# emonPi_v2_0_0_CT_ext.net
KiCad netlist of a schematic drawn in EAGLE
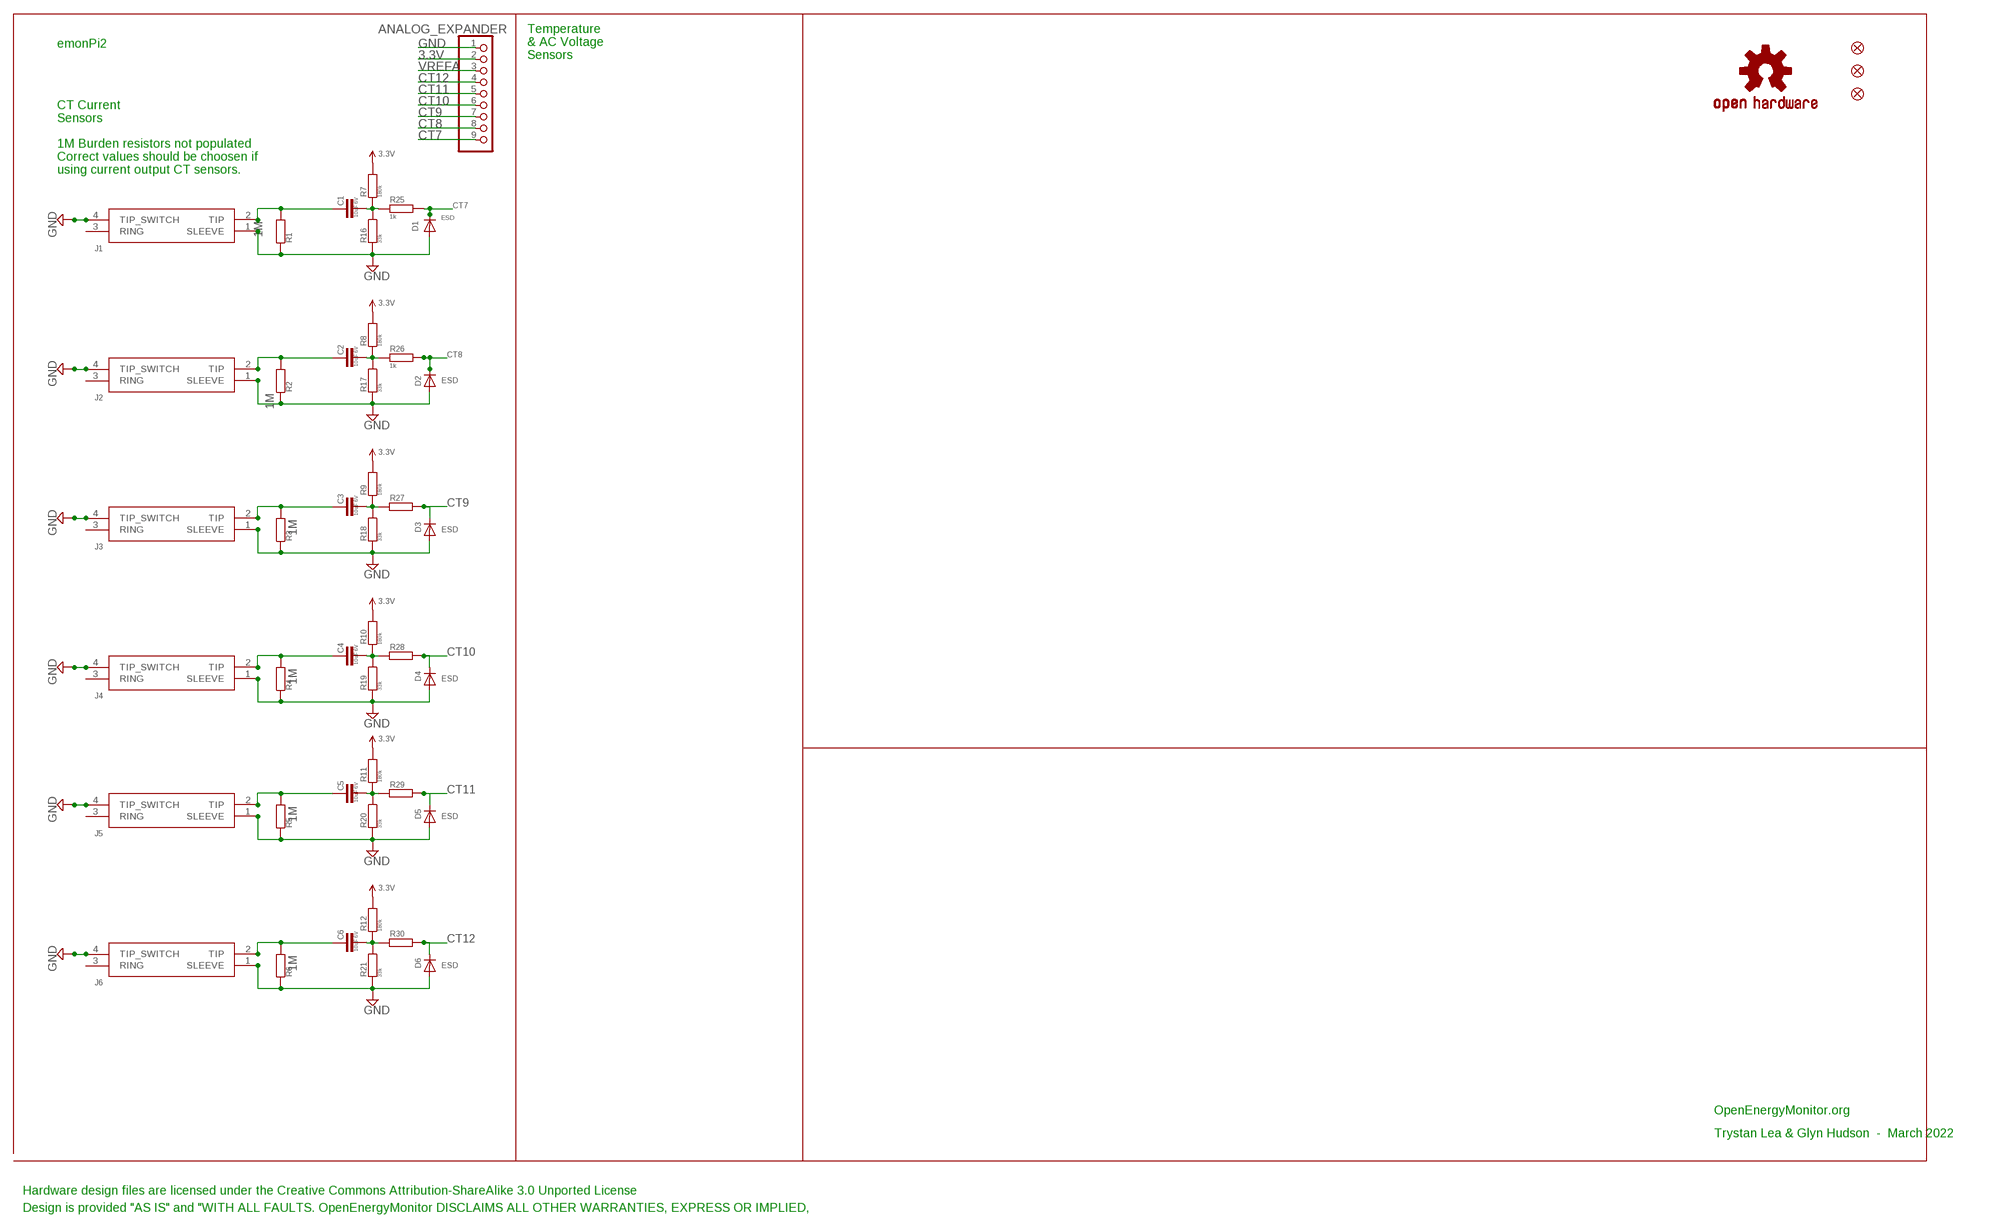
[diagram p0: schematic, sheet 1]

(export (version "E")
  (design (tool "Eeschema 10.0.6"))
  (components
    (comp (ref "ANALOG_EXPANDER")
      (value "PINHD-1X9")
      (footprint "eagle-import:1X09-BIG")
      (libsource (lib "eagle-import") (part "PINHD-1X9"))
    )
    (comp (ref "C1")
      (value "10uF 6V")
      (footprint "eagle-import:C0603")
      (libsource (lib "eagle-import") (part "C-EUC0603"))
    )
    (comp (ref "C2")
      (value "10uF 6V")
      (footprint "eagle-import:C0603")
      (libsource (lib "eagle-import") (part "C-EUC0603"))
    )
    (comp (ref "C3")
      (value "10uF 6V")
      (footprint "eagle-import:C0603")
      (libsource (lib "eagle-import") (part "C-EUC0603"))
    )
    (comp (ref "C4")
      (value "10uF 6V")
      (footprint "eagle-import:C0603")
      (libsource (lib "eagle-import") (part "C-EUC0603"))
    )
    (comp (ref "C5")
      (value "10uF 6V")
      (footprint "eagle-import:C0603")
      (libsource (lib "eagle-import") (part "C-EUC0603"))
    )
    (comp (ref "C6")
      (value "10uF 6V")
      (footprint "eagle-import:C0603")
      (libsource (lib "eagle-import") (part "C-EUC0603"))
    )
    (comp (ref "D1")
      (value "ESD")
      (footprint "eagle-import:SOD-523")
      (libsource (lib "eagle-import") (part "DIODESOD-523"))
    )
    (comp (ref "D2")
      (value "ESD")
      (footprint "eagle-import:SOD-523")
      (libsource (lib "eagle-import") (part "DIODESOD-523"))
    )
    (comp (ref "D3")
      (value "ESD")
      (footprint "eagle-import:SOD-523")
      (libsource (lib "eagle-import") (part "DIODESOD-523"))
    )
    (comp (ref "D4")
      (value "ESD")
      (footprint "eagle-import:SOD-523")
      (libsource (lib "eagle-import") (part "DIODESOD-523"))
    )
    (comp (ref "D5")
      (value "ESD")
      (footprint "eagle-import:SOD-523")
      (libsource (lib "eagle-import") (part "DIODESOD-523"))
    )
    (comp (ref "D6")
      (value "ESD")
      (footprint "eagle-import:SOD-523")
      (libsource (lib "eagle-import") (part "DIODESOD-523"))
    )
    (comp (ref "FD1")
      (value "FIDUCIAL1X2")
      (footprint "eagle-import:FIDUCIAL-1X2")
      (libsource (lib "eagle-import") (part "FIDUCIAL1X2"))
    )
    (comp (ref "FD2")
      (value "FIDUCIAL1X2")
      (footprint "eagle-import:FIDUCIAL-1X2")
      (libsource (lib "eagle-import") (part "FIDUCIAL1X2"))
    )
    (comp (ref "FD3")
      (value "FIDUCIAL1X2")
      (footprint "eagle-import:FIDUCIAL-1X2")
      (libsource (lib "eagle-import") (part "FIDUCIAL1X2"))
    )
    (comp (ref "J1")
      (value "SJ-3524-SMT-TR")
      (footprint "eagle-import:SJ-3524-SMT-TR")
      (fields (field (name "MOUSER_PART_NUMBER") "490-SJ-3524-SMT-TR"))
      (libsource (lib "eagle-import") (part "SJ-3524-SMT-TR"))
    )
    (comp (ref "J2")
      (value "SJ-3524-SMT-TR")
      (footprint "eagle-import:SJ-3524-SMT-TR")
      (fields (field (name "MOUSER_PART_NUMBER") "490-SJ-3524-SMT-TR"))
      (libsource (lib "eagle-import") (part "SJ-3524-SMT-TR"))
    )
    (comp (ref "J3")
      (value "SJ-3524-SMT-TR")
      (footprint "eagle-import:SJ-3524-SMT-TR")
      (fields (field (name "MOUSER_PART_NUMBER") "490-SJ-3524-SMT-TR"))
      (libsource (lib "eagle-import") (part "SJ-3524-SMT-TR"))
    )
    (comp (ref "J4")
      (value "SJ-3524-SMT-TR")
      (footprint "eagle-import:SJ-3524-SMT-TR")
      (fields (field (name "MOUSER_PART_NUMBER") "490-SJ-3524-SMT-TR"))
      (libsource (lib "eagle-import") (part "SJ-3524-SMT-TR"))
    )
    (comp (ref "J5")
      (value "SJ-3524-SMT-TR")
      (footprint "eagle-import:SJ-3524-SMT-TR")
      (fields (field (name "MOUSER_PART_NUMBER") "490-SJ-3524-SMT-TR"))
      (libsource (lib "eagle-import") (part "SJ-3524-SMT-TR"))
    )
    (comp (ref "J6")
      (value "SJ-3524-SMT-TR")
      (footprint "eagle-import:SJ-3524-SMT-TR")
      (fields (field (name "MOUSER_PART_NUMBER") "490-SJ-3524-SMT-TR"))
      (libsource (lib "eagle-import") (part "SJ-3524-SMT-TR"))
    )
    (comp (ref "LOGO1")
      (value "OSHW-LOGOS-COPPER")
      (footprint "eagle-import:OSHW-LOGO-S_COPPER")
      (libsource (lib "eagle-import") (part "OSHW-LOGOS-COPPER"))
    )
    (comp (ref "R1")
      (value "1M")
      (footprint "eagle-import:R1206")
      (libsource (lib "eagle-import") (part "R-EU_R1206"))
    )
    (comp (ref "R2")
      (value "1M")
      (footprint "eagle-import:R1206")
      (libsource (lib "eagle-import") (part "R-EU_R1206"))
    )
    (comp (ref "R3")
      (value "1M")
      (footprint "eagle-import:R1206")
      (libsource (lib "eagle-import") (part "R-EU_R1206"))
    )
    (comp (ref "R4")
      (value "1M")
      (footprint "eagle-import:R1206")
      (libsource (lib "eagle-import") (part "R-EU_R1206"))
    )
    (comp (ref "R5")
      (value "1M")
      (footprint "eagle-import:R1206")
      (libsource (lib "eagle-import") (part "R-EU_R1206"))
    )
    (comp (ref "R6")
      (value "1M")
      (footprint "eagle-import:R1206")
      (libsource (lib "eagle-import") (part "R-EU_R1206"))
    )
    (comp (ref "R7")
      (value "180k")
      (footprint "eagle-import:R0603")
      (libsource (lib "eagle-import") (part "R-EU_R0603"))
    )
    (comp (ref "R8")
      (value "180k")
      (footprint "eagle-import:R0603")
      (libsource (lib "eagle-import") (part "R-EU_R0603"))
    )
    (comp (ref "R9")
      (value "180k")
      (footprint "eagle-import:R0603")
      (libsource (lib "eagle-import") (part "R-EU_R0603"))
    )
    (comp (ref "R10")
      (value "180k")
      (footprint "eagle-import:R0603")
      (libsource (lib "eagle-import") (part "R-EU_R0603"))
    )
    (comp (ref "R11")
      (value "180k")
      (footprint "eagle-import:R0603")
      (libsource (lib "eagle-import") (part "R-EU_R0603"))
    )
    (comp (ref "R12")
      (value "180k")
      (footprint "eagle-import:R0603")
      (libsource (lib "eagle-import") (part "R-EU_R0603"))
    )
    (comp (ref "R16")
      (value "33k")
      (footprint "eagle-import:R0603")
      (libsource (lib "eagle-import") (part "R-EU_R0603"))
    )
    (comp (ref "R17")
      (value "33k")
      (footprint "eagle-import:R0603")
      (libsource (lib "eagle-import") (part "R-EU_R0603"))
    )
    (comp (ref "R18")
      (value "33k")
      (footprint "eagle-import:R0603")
      (libsource (lib "eagle-import") (part "R-EU_R0603"))
    )
    (comp (ref "R19")
      (value "33k")
      (footprint "eagle-import:R0603")
      (libsource (lib "eagle-import") (part "R-EU_R0603"))
    )
    (comp (ref "R20")
      (value "33k")
      (footprint "eagle-import:R0603")
      (libsource (lib "eagle-import") (part "R-EU_R0603"))
    )
    (comp (ref "R21")
      (value "33k")
      (footprint "eagle-import:R0603")
      (libsource (lib "eagle-import") (part "R-EU_R0603"))
    )
    (comp (ref "R25")
      (value "1k")
      (footprint "eagle-import:R0603")
      (libsource (lib "eagle-import") (part "R-EU_R0603"))
    )
    (comp (ref "R26")
      (value "1k")
      (footprint "eagle-import:R0603")
      (libsource (lib "eagle-import") (part "R-EU_R0603"))
    )
    (comp (ref "R27")
      (value "1k")
      (footprint "eagle-import:R0603")
      (libsource (lib "eagle-import") (part "R-EU_R0603"))
    )
    (comp (ref "R28")
      (value "1k")
      (footprint "eagle-import:R0603")
      (libsource (lib "eagle-import") (part "R-EU_R0603"))
    )
    (comp (ref "R29")
      (value "1k")
      (footprint "eagle-import:R0603")
      (libsource (lib "eagle-import") (part "R-EU_R0603"))
    )
    (comp (ref "R30")
      (value "1k")
      (footprint "eagle-import:R0603")
      (libsource (lib "eagle-import") (part "R-EU_R0603"))
    )
  )
  (nets
    (net (code "1") (name "/CT7") (class "Default")
      (node (ref "ANALOG_EXPANDER") (pin "9") (pinfunction "9_9") (pintype "passive"))
      (node (ref "D1") (pin "K") (pinfunction "C_K") (pintype "passive"))
      (node (ref "R25") (pin "2") (pinfunction "2_2") (pintype "passive"))
    )
    (net (code "2") (name "/CT8") (class "Default")
      (node (ref "ANALOG_EXPANDER") (pin "8") (pinfunction "8_8") (pintype "passive"))
      (node (ref "D2") (pin "K") (pinfunction "C_K") (pintype "passive"))
      (node (ref "R26") (pin "2") (pinfunction "2_2") (pintype "passive"))
    )
    (net (code "3") (name "/CT9") (class "Default")
      (node (ref "ANALOG_EXPANDER") (pin "7") (pinfunction "7_7") (pintype "passive"))
      (node (ref "D3") (pin "K") (pinfunction "C_K") (pintype "passive"))
      (node (ref "R27") (pin "1") (pinfunction "1_1") (pintype "passive"))
    )
    (net (code "4") (name "/CT10") (class "Default")
      (node (ref "ANALOG_EXPANDER") (pin "6") (pinfunction "6_6") (pintype "passive"))
      (node (ref "D4") (pin "K") (pinfunction "C_K") (pintype "passive"))
      (node (ref "R28") (pin "1") (pinfunction "1_1") (pintype "passive"))
    )
    (net (code "5") (name "/CT11") (class "Default")
      (node (ref "ANALOG_EXPANDER") (pin "5") (pinfunction "5_5") (pintype "passive"))
      (node (ref "D5") (pin "K") (pinfunction "C_K") (pintype "passive"))
      (node (ref "R29") (pin "1") (pinfunction "1_1") (pintype "passive"))
    )
    (net (code "6") (name "/CT12") (class "Default")
      (node (ref "ANALOG_EXPANDER") (pin "4") (pinfunction "4_4") (pintype "passive"))
      (node (ref "D6") (pin "K") (pinfunction "C_K") (pintype "passive"))
      (node (ref "R30") (pin "1") (pinfunction "1_1") (pintype "passive"))
    )
    (net (code "7") (name "/VREFA") (class "Default")
      (node (ref "ANALOG_EXPANDER") (pin "3") (pinfunction "3_3") (pintype "passive"))
    )
    (net (code "8") (name "3.3V") (class "Default")
      (node (ref "ANALOG_EXPANDER") (pin "2") (pinfunction "2_2") (pintype "passive"))
      (node (ref "R10") (pin "2") (pinfunction "2_2") (pintype "passive"))
      (node (ref "R11") (pin "2") (pinfunction "2_2") (pintype "passive"))
      (node (ref "R12") (pin "2") (pinfunction "2_2") (pintype "passive"))
      (node (ref "R7") (pin "2") (pinfunction "2_2") (pintype "passive"))
      (node (ref "R8") (pin "2") (pinfunction "2_2") (pintype "passive"))
      (node (ref "R9") (pin "2") (pinfunction "2_2") (pintype "passive"))
    )
    (net (code "9") (name "GND") (class "Default")
      (node (ref "ANALOG_EXPANDER") (pin "1") (pinfunction "1_1") (pintype "passive"))
      (node (ref "D1") (pin "A") (pinfunction "A_A") (pintype "passive"))
      (node (ref "D2") (pin "A") (pinfunction "A_A") (pintype "passive"))
      (node (ref "D3") (pin "A") (pinfunction "A_A") (pintype "passive"))
      (node (ref "D4") (pin "A") (pinfunction "A_A") (pintype "passive"))
      (node (ref "D5") (pin "A") (pinfunction "A_A") (pintype "passive"))
      (node (ref "D6") (pin "A") (pinfunction "A_A") (pintype "passive"))
      (node (ref "J1") (pin "1") (pinfunction "SLEEVE_1") (pintype "bidirectional"))
      (node (ref "J1") (pin "4") (pinfunction "TIP_SWITCH_4") (pintype "bidirectional"))
      (node (ref "J2") (pin "1") (pinfunction "SLEEVE_1") (pintype "bidirectional"))
      (node (ref "J2") (pin "4") (pinfunction "TIP_SWITCH_4") (pintype "bidirectional"))
      (node (ref "J3") (pin "1") (pinfunction "SLEEVE_1") (pintype "bidirectional"))
      (node (ref "J3") (pin "4") (pinfunction "TIP_SWITCH_4") (pintype "bidirectional"))
      (node (ref "J4") (pin "1") (pinfunction "SLEEVE_1") (pintype "bidirectional"))
      (node (ref "J4") (pin "4") (pinfunction "TIP_SWITCH_4") (pintype "bidirectional"))
      (node (ref "J5") (pin "1") (pinfunction "SLEEVE_1") (pintype "bidirectional"))
      (node (ref "J5") (pin "4") (pinfunction "TIP_SWITCH_4") (pintype "bidirectional"))
      (node (ref "J6") (pin "1") (pinfunction "SLEEVE_1") (pintype "bidirectional"))
      (node (ref "J6") (pin "4") (pinfunction "TIP_SWITCH_4") (pintype "bidirectional"))
      (node (ref "R1") (pin "1") (pinfunction "1_1") (pintype "passive"))
      (node (ref "R16") (pin "2") (pinfunction "2_2") (pintype "passive"))
      (node (ref "R17") (pin "2") (pinfunction "2_2") (pintype "passive"))
      (node (ref "R18") (pin "2") (pinfunction "2_2") (pintype "passive"))
      (node (ref "R19") (pin "2") (pinfunction "2_2") (pintype "passive"))
      (node (ref "R2") (pin "1") (pinfunction "1_1") (pintype "passive"))
      (node (ref "R20") (pin "2") (pinfunction "2_2") (pintype "passive"))
      (node (ref "R21") (pin "2") (pinfunction "2_2") (pintype "passive"))
      (node (ref "R3") (pin "1") (pinfunction "1_1") (pintype "passive"))
      (node (ref "R4") (pin "1") (pinfunction "1_1") (pintype "passive"))
      (node (ref "R5") (pin "1") (pinfunction "1_1") (pintype "passive"))
      (node (ref "R6") (pin "1") (pinfunction "1_1") (pintype "passive"))
    )
    (net (code "10") (name "Net-(C1-Pad2)") (class "Default")
      (node (ref "C1") (pin "2") (pinfunction "2_2") (pintype "passive"))
      (node (ref "R16") (pin "1") (pinfunction "1_1") (pintype "passive"))
      (node (ref "R25") (pin "1") (pinfunction "1_1") (pintype "passive"))
      (node (ref "R7") (pin "1") (pinfunction "1_1") (pintype "passive"))
    )
    (net (code "11") (name "Net-(C2-Pad2)") (class "Default")
      (node (ref "C2") (pin "2") (pinfunction "2_2") (pintype "passive"))
      (node (ref "R17") (pin "1") (pinfunction "1_1") (pintype "passive"))
      (node (ref "R26") (pin "1") (pinfunction "1_1") (pintype "passive"))
      (node (ref "R8") (pin "1") (pinfunction "1_1") (pintype "passive"))
    )
    (net (code "12") (name "Net-(C3-Pad2)") (class "Default")
      (node (ref "C3") (pin "2") (pinfunction "2_2") (pintype "passive"))
      (node (ref "R18") (pin "1") (pinfunction "1_1") (pintype "passive"))
      (node (ref "R27") (pin "2") (pinfunction "2_2") (pintype "passive"))
      (node (ref "R9") (pin "1") (pinfunction "1_1") (pintype "passive"))
    )
    (net (code "13") (name "Net-(C4-Pad2)") (class "Default")
      (node (ref "C4") (pin "2") (pinfunction "2_2") (pintype "passive"))
      (node (ref "R10") (pin "1") (pinfunction "1_1") (pintype "passive"))
      (node (ref "R19") (pin "1") (pinfunction "1_1") (pintype "passive"))
      (node (ref "R28") (pin "2") (pinfunction "2_2") (pintype "passive"))
    )
    (net (code "14") (name "Net-(C5-Pad2)") (class "Default")
      (node (ref "C5") (pin "2") (pinfunction "2_2") (pintype "passive"))
      (node (ref "R11") (pin "1") (pinfunction "1_1") (pintype "passive"))
      (node (ref "R20") (pin "1") (pinfunction "1_1") (pintype "passive"))
      (node (ref "R29") (pin "2") (pinfunction "2_2") (pintype "passive"))
    )
    (net (code "15") (name "Net-(C6-Pad2)") (class "Default")
      (node (ref "C6") (pin "2") (pinfunction "2_2") (pintype "passive"))
      (node (ref "R12") (pin "1") (pinfunction "1_1") (pintype "passive"))
      (node (ref "R21") (pin "1") (pinfunction "1_1") (pintype "passive"))
      (node (ref "R30") (pin "2") (pinfunction "2_2") (pintype "passive"))
    )
    (net (code "16") (name "Net-(J1-TIP)") (class "Default")
      (node (ref "C1") (pin "1") (pinfunction "1_1") (pintype "passive"))
      (node (ref "J1") (pin "2") (pinfunction "TIP_2") (pintype "bidirectional"))
      (node (ref "R1") (pin "2") (pinfunction "2_2") (pintype "passive"))
    )
    (net (code "17") (name "Net-(J2-TIP)") (class "Default")
      (node (ref "C2") (pin "1") (pinfunction "1_1") (pintype "passive"))
      (node (ref "J2") (pin "2") (pinfunction "TIP_2") (pintype "bidirectional"))
      (node (ref "R2") (pin "2") (pinfunction "2_2") (pintype "passive"))
    )
    (net (code "18") (name "Net-(J3-TIP)") (class "Default")
      (node (ref "C3") (pin "1") (pinfunction "1_1") (pintype "passive"))
      (node (ref "J3") (pin "2") (pinfunction "TIP_2") (pintype "bidirectional"))
      (node (ref "R3") (pin "2") (pinfunction "2_2") (pintype "passive"))
    )
    (net (code "19") (name "Net-(J4-TIP)") (class "Default")
      (node (ref "C4") (pin "1") (pinfunction "1_1") (pintype "passive"))
      (node (ref "J4") (pin "2") (pinfunction "TIP_2") (pintype "bidirectional"))
      (node (ref "R4") (pin "2") (pinfunction "2_2") (pintype "passive"))
    )
    (net (code "20") (name "Net-(J5-TIP)") (class "Default")
      (node (ref "C5") (pin "1") (pinfunction "1_1") (pintype "passive"))
      (node (ref "J5") (pin "2") (pinfunction "TIP_2") (pintype "bidirectional"))
      (node (ref "R5") (pin "2") (pinfunction "2_2") (pintype "passive"))
    )
    (net (code "21") (name "Net-(J6-TIP)") (class "Default")
      (node (ref "C6") (pin "1") (pinfunction "1_1") (pintype "passive"))
      (node (ref "J6") (pin "2") (pinfunction "TIP_2") (pintype "bidirectional"))
      (node (ref "R6") (pin "2") (pinfunction "2_2") (pintype "passive"))
    )
    (net (code "22") (name "unconnected-(J1-RING-Pad3)") (class "Default")
      (node (ref "J1") (pin "3") (pinfunction "RING_3") (pintype "bidirectional"))
    )
    (net (code "23") (name "unconnected-(J2-RING-Pad3)") (class "Default")
      (node (ref "J2") (pin "3") (pinfunction "RING_3") (pintype "bidirectional"))
    )
    (net (code "24") (name "unconnected-(J3-RING-Pad3)") (class "Default")
      (node (ref "J3") (pin "3") (pinfunction "RING_3") (pintype "bidirectional"))
    )
    (net (code "25") (name "unconnected-(J4-RING-Pad3)") (class "Default")
      (node (ref "J4") (pin "3") (pinfunction "RING_3") (pintype "bidirectional"))
    )
    (net (code "26") (name "unconnected-(J5-RING-Pad3)") (class "Default")
      (node (ref "J5") (pin "3") (pinfunction "RING_3") (pintype "bidirectional"))
    )
    (net (code "27") (name "unconnected-(J6-RING-Pad3)") (class "Default")
      (node (ref "J6") (pin "3") (pinfunction "RING_3") (pintype "bidirectional"))
    )
  )
)
